# schematic.net
KiCad netlist of a schematic drawn in EasyEDA
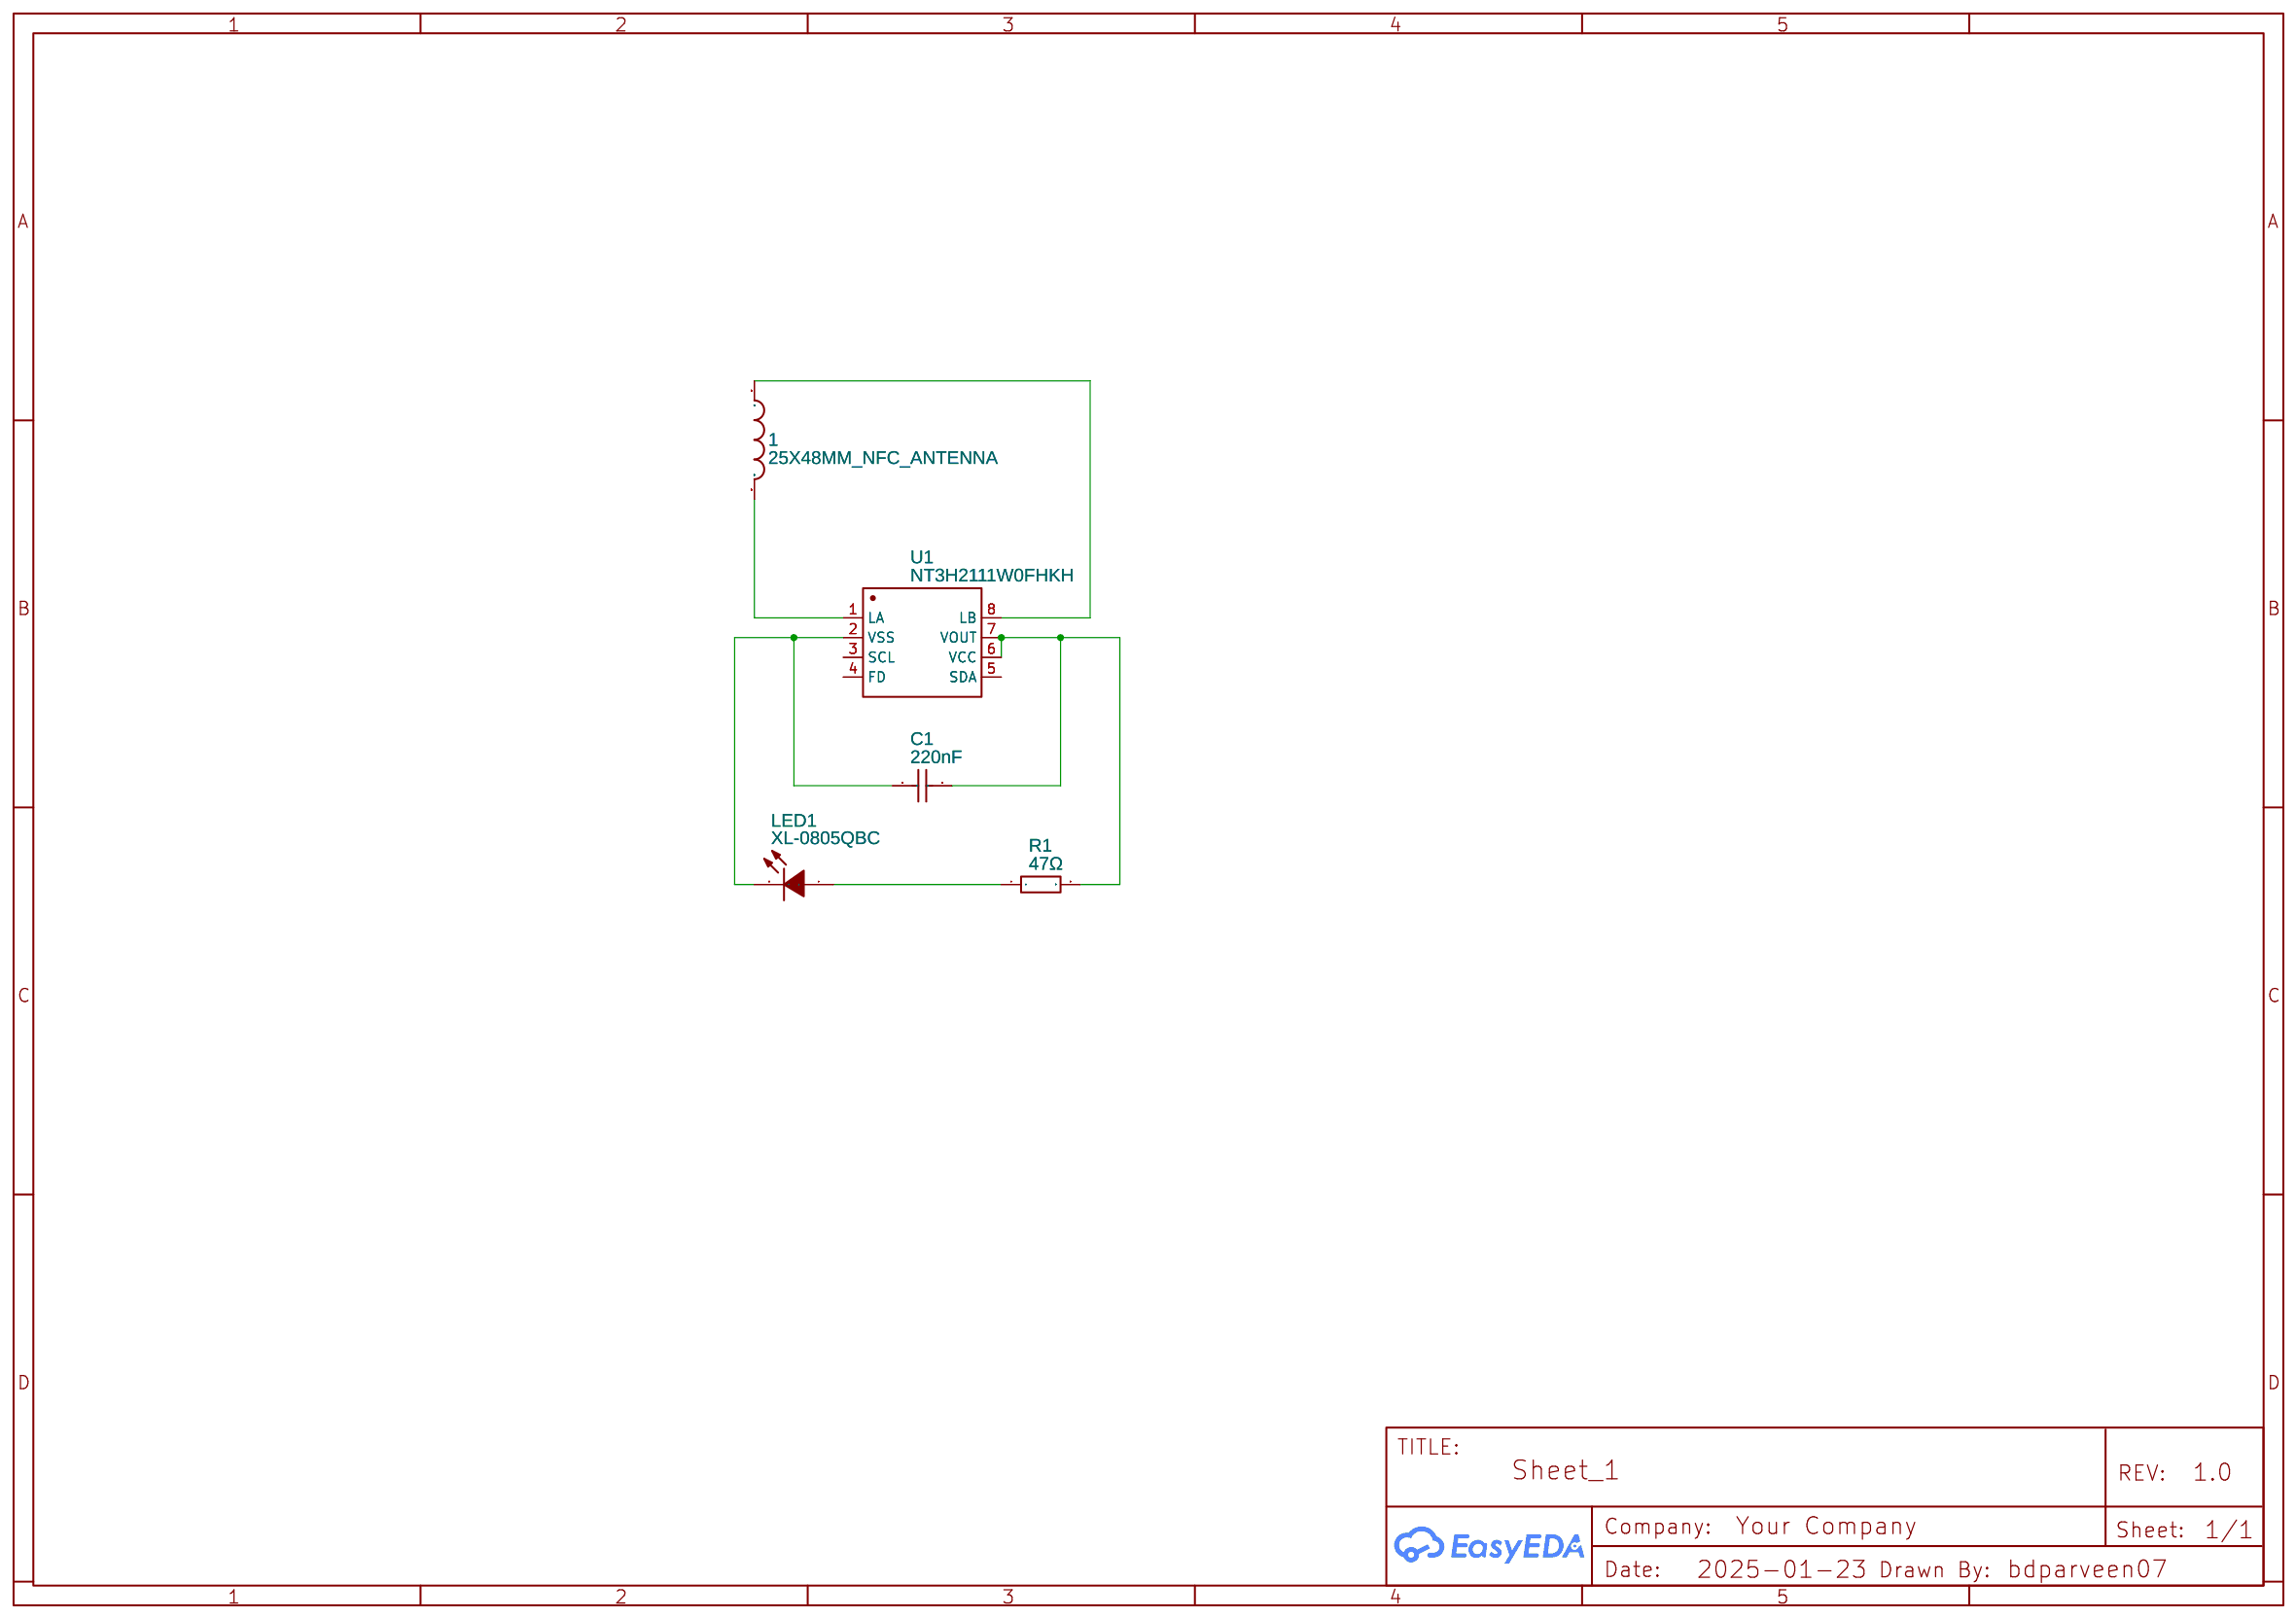
[diagram p0: schematic sheet]

(export (version "E")
  (design (tool "Eeschema 10.0.6"))
  (components
    (comp (ref "1") (value "25X48MM_NFC_ANTENNA") (libsource (lib "") (part "25X48MM_NFC_ANTENNA")))
    (comp (ref "C1")
      (value "220nF")
      (fields
        (field (name "Manufacturer Part") "CL10B224KA8NNNC")
        (field (name "Manufacturer") "SAMSUNG(三星)")
      )
      (libsource (lib "") (part "CL10B224KA8NNNC"))
    )
    (comp (ref "LED1")
      (value "XL-0805QBC")
      (fields (field (name "Manufacturer Part") "KT-0805B") (field (name "Manufacturer") "KENTO"))
      (libsource (lib "") (part "XL-0805QBC"))
    )
    (comp (ref "R1")
      (value "47Ω")
      (fields
        (field (name "Manufacturer Part") "0603WAF470JT5E")
        (field (name "Manufacturer") "UNI-ROYAL(厚声)")
      )
      (libsource (lib "") (part "0603WAF470JT5E"))
    )
    (comp (ref "U1")
      (value "NT3H2111W0FHKH")
      (fields (field (name "Manufacturer") "NXP(恩智浦)"))
      (libsource (lib "") (part "NT3H2111W0FHKH"))
    )
  )
  (nets
    (net (code "1") (name "Net-(LED1-A)") (class "Default")
      (node (ref "LED1") (pin "1") (pinfunction "A_1") (pintype "unspecified"))
      (node (ref "R1") (pin "1") (pinfunction "1_1") (pintype "input"))
    )
    (net (code "2") (name "Net-(LED1-K)") (class "Default")
      (node (ref "C1") (pin "1") (pinfunction "1_1") (pintype "input"))
      (node (ref "LED1") (pin "2") (pinfunction "K_2") (pintype "unspecified"))
      (node (ref "U1") (pin "2") (pinfunction "VSS_2") (pintype "unspecified"))
    )
    (net (code "3") (name "Net-(U1-LA)") (class "Default")
      (node (ref "1") (pin "P$2") (pinfunction "P$2_P$2") (pintype "bidirectional"))
      (node (ref "U1") (pin "1") (pinfunction "LA_1") (pintype "unspecified"))
    )
    (net (code "4") (name "Net-(U1-LB)") (class "Default")
      (node (ref "1") (pin "P$1") (pinfunction "P$1_P$1") (pintype "bidirectional"))
      (node (ref "U1") (pin "8") (pinfunction "LB_8") (pintype "unspecified"))
    )
    (net (code "5") (name "Net-(U1-VCC)") (class "Default")
      (node (ref "C1") (pin "2") (pinfunction "2_2") (pintype "input"))
      (node (ref "R1") (pin "2") (pinfunction "2_2") (pintype "input"))
      (node (ref "U1") (pin "6") (pinfunction "VCC_6") (pintype "unspecified"))
      (node (ref "U1") (pin "7") (pinfunction "VOUT_7") (pintype "unspecified"))
    )
    (net (code "6") (name "unconnected-(U1-FD-Pad4)") (class "Default")
      (node (ref "U1") (pin "4") (pinfunction "FD_4") (pintype "unspecified"))
    )
    (net (code "7") (name "unconnected-(U1-SCL-Pad3)") (class "Default")
      (node (ref "U1") (pin "3") (pinfunction "SCL_3") (pintype "unspecified"))
    )
    (net (code "8") (name "unconnected-(U1-SDA-Pad5)") (class "Default")
      (node (ref "U1") (pin "5") (pinfunction "SDA_5") (pintype "unspecified"))
    )
  )
)
